# POWER.net
KiCad netlist of a schematic drawn in Altium Designer
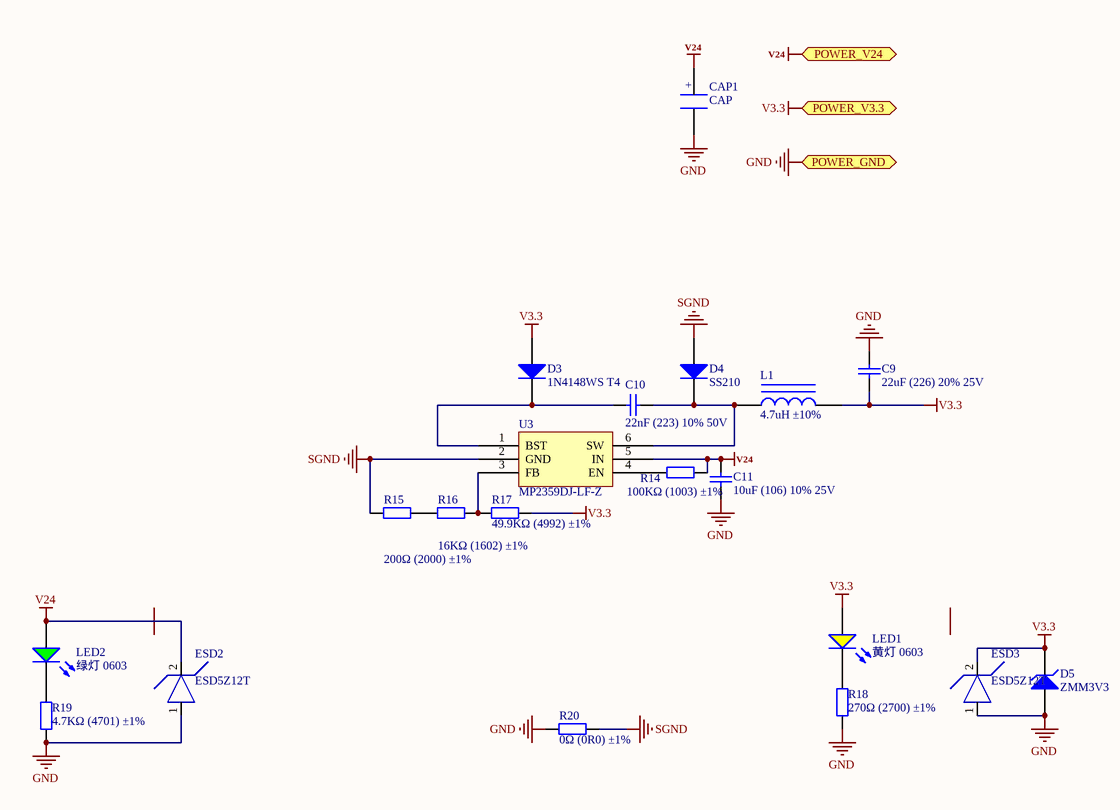
[diagram p0: POWER.SchDoc]

(export (version "E")
  (design (tool "Eeschema 10.0.6"))
  (components
    (comp (ref "C9")
      (value "22uF (226) 20% 25V")
      (footprint "0805_C")
      (description "贴片电容")
      (libsource (lib "Miscellaneous Devices LC") (part "0805 22uF (226) 20% 25V"))
    )
    (comp (ref "C10")
      (value "22nF (223) 10% 50V")
      (footprint "0603_C")
      (description "贴片电容")
      (libsource (lib "Miscellaneous Devices LC") (part "0603 22nF (223) 10% 50V"))
    )
    (comp (ref "C11")
      (value "10uF (106) 10% 25V")
      (footprint "0805_C")
      (description "贴片电容")
      (libsource (lib "Miscellaneous Devices LC") (part "0805 10uF (106) 10% 25V"))
    )
    (comp (ref "CAP1") (value "CAP") (footprint "8X12_CAP") (libsource (lib "mylib") (part "CAP")))
    (comp (ref "D3")
      (value "1N4148WS T4")
      (footprint "SOD-323")
      (description "二极管")
      (libsource (lib "Miscellaneous Devices LC") (part "SOD-323 1N4148WS T4"))
    )
    (comp (ref "D4")
      (value "SS210")
      (footprint "SMA(DO-214AC)_S1")
      (description "二极管")
      (libsource (lib "Miscellaneous Devices LC") (part "SMA(DO-214AC) SS210"))
    )
    (comp (ref "D5")
      (value "ZMM3V3")
      (footprint "LL-34")
      (description "稳压二极管")
      (libsource (lib "Miscellaneous Devices LC") (part "LL-34 ZMM3V3"))
    )
    (comp (ref "ESD2") (value "ESD5Z12T") (footprint "SOD-523") (libsource (lib "mylib") (part "ESD-D")))
    (comp (ref "ESD3") (value "ESD5Z12T") (footprint "SOD-523") (libsource (lib "mylib") (part "ESD-D")))
    (comp (ref "L1")
      (value "4.7uH ±10%")
      (footprint "L_4030")
      (description "贴片电感")
      (libsource (lib "Miscellaneous Devices LC") (part "0603 4.7uH 10%"))
    )
    (comp (ref "LED1")
      (value "黄灯 0603")
      (footprint "0603_LED_S1")
      (description "发光二极管")
      (libsource (lib "Miscellaneous Devices LC") (part "0603 黄灯"))
    )
    (comp (ref "LED2")
      (value "绿灯 0603")
      (footprint "0603_LED_S1")
      (description "发光二极管")
      (libsource (lib "Miscellaneous Devices LC") (part "0603 绿灯"))
    )
    (comp (ref "R14")
      (value "100KΩ (1003) ±1%")
      (footprint "0603_R")
      (description "贴片电阻")
      (libsource (lib "Miscellaneous Devices LC") (part "0603 100KΩ (1003) 1%"))
    )
    (comp (ref "R15")
      (value "200Ω (2000) ±1%")
      (footprint "0603_R")
      (description "贴片电阻")
      (libsource (lib "Miscellaneous Devices LC") (part "0603 200Ω (2000) 1%"))
    )
    (comp (ref "R16")
      (value "16KΩ (1602) ±1%")
      (footprint "0603_R")
      (description "贴片电阻")
      (libsource (lib "Miscellaneous Devices LC") (part "0603 16KΩ (1602) 1%"))
    )
    (comp (ref "R17")
      (value "49.9KΩ (4992) ±1%")
      (footprint "0603_R")
      (description "贴片电阻")
      (libsource (lib "Miscellaneous Devices LC") (part "0603 49.9KΩ (4992) 1%"))
    )
    (comp (ref "R18")
      (value "270Ω (2700) ±1%")
      (footprint "0805_R")
      (description "贴片电阻")
      (libsource (lib "Miscellaneous Devices LC") (part "0805 270Ω (2700) 1%"))
    )
    (comp (ref "R19")
      (value "4.7KΩ (4701) ±1%")
      (footprint "0805_R")
      (description "贴片电阻")
      (libsource (lib "Miscellaneous Devices LC") (part "0805 4.7KΩ (4701) 1%"))
    )
    (comp (ref "R20")
      (value "0Ω (0R0) ±1%")
      (footprint "0603_R")
      (description "贴片电阻")
      (libsource (lib "Miscellaneous Devices LC") (part "0603 0Ω (0R0) 1%"))
    )
    (comp (ref "U3")
      (value "MP2359DJ-LF-Z")
      (footprint "SOT-23-6")
      (description "DC-DC芯片")
      (libsource (lib "Miscellaneous Devices LC") (part "MP2359DJ-LF-Z_[C14259]"))
    )
  )
  (nets
    (net (code "1") (name "GND") (class "Default")
      (node (ref "C11") (pin "1") (pinfunction "1_1") (pintype "passive"))
      (node (ref "C9") (pin "2") (pinfunction "2_2") (pintype "passive"))
      (node (ref "CAP1") (pin "2") (pinfunction "2_2") (pintype "passive"))
      (node (ref "D5") (pin "1") (pinfunction "A_1") (pintype "passive"))
      (node (ref "ESD2") (pin "1") (pinfunction "1_1") (pintype "passive"))
      (node (ref "ESD3") (pin "1") (pinfunction "1_1") (pintype "passive"))
      (node (ref "R18") (pin "1") (pinfunction "1_1") (pintype "passive"))
      (node (ref "R19") (pin "1") (pinfunction "1_1") (pintype "passive"))
      (node (ref "R20") (pin "1") (pinfunction "1_1") (pintype "passive"))
    )
    (net (code "2") (name "Net-(D3-K)") (class "Default")
      (node (ref "C10") (pin "1") (pinfunction "1_1") (pintype "passive"))
      (node (ref "D3") (pin "2") (pinfunction "K_2") (pintype "passive"))
      (node (ref "U3") (pin "1") (pinfunction "BST_1") (pintype "passive"))
    )
    (net (code "3") (name "Net-(D4-K)") (class "Default")
      (node (ref "C10") (pin "2") (pinfunction "2_2") (pintype "passive"))
      (node (ref "D4") (pin "2") (pinfunction "K_2") (pintype "passive"))
      (node (ref "L1") (pin "1") (pinfunction "1_1") (pintype "passive"))
      (node (ref "U3") (pin "6") (pinfunction "SW_6") (pintype "passive"))
    )
    (net (code "4") (name "Net-(LED1-PadK)") (class "Default")
      (node (ref "LED1") (pin "K") (pinfunction "K_K") (pintype "passive"))
      (node (ref "R18") (pin "2") (pinfunction "2_2") (pintype "passive"))
    )
    (net (code "5") (name "Net-(LED2-PadK)") (class "Default")
      (node (ref "LED2") (pin "K") (pinfunction "K_K") (pintype "passive"))
      (node (ref "R19") (pin "2") (pinfunction "2_2") (pintype "passive"))
    )
    (net (code "6") (name "Net-(R15-Pad1)") (class "Default")
      (node (ref "R15") (pin "1") (pinfunction "1_1") (pintype "passive"))
      (node (ref "R16") (pin "2") (pinfunction "2_2") (pintype "passive"))
    )
    (net (code "7") (name "Net-(U3-EN)") (class "Default")
      (node (ref "R14") (pin "1") (pinfunction "1_1") (pintype "passive"))
      (node (ref "U3") (pin "4") (pinfunction "EN_4") (pintype "passive"))
    )
    (net (code "8") (name "Net-(U3-FB)") (class "Default")
      (node (ref "R16") (pin "1") (pinfunction "1_1") (pintype "passive"))
      (node (ref "R17") (pin "1") (pinfunction "1_1") (pintype "passive"))
      (node (ref "U3") (pin "3") (pinfunction "FB_3") (pintype "passive"))
    )
    (net (code "9") (name "SGND") (class "Default")
      (node (ref "D4") (pin "1") (pinfunction "A_1") (pintype "passive"))
      (node (ref "R15") (pin "2") (pinfunction "2_2") (pintype "passive"))
      (node (ref "R20") (pin "2") (pinfunction "2_2") (pintype "passive"))
      (node (ref "U3") (pin "2") (pinfunction "GND_2") (pintype "passive"))
    )
    (net (code "10") (name "V3.3") (class "Default")
      (node (ref "C9") (pin "1") (pinfunction "1_1") (pintype "passive"))
      (node (ref "D3") (pin "1") (pinfunction "A_1") (pintype "passive"))
      (node (ref "D5") (pin "2") (pinfunction "K_2") (pintype "passive"))
      (node (ref "ESD3") (pin "2") (pinfunction "2_2") (pintype "passive"))
      (node (ref "L1") (pin "2") (pinfunction "2_2") (pintype "passive"))
      (node (ref "LED1") (pin "A") (pinfunction "A_A") (pintype "passive"))
      (node (ref "R17") (pin "2") (pinfunction "2_2") (pintype "passive"))
    )
    (net (code "11") (name "V24") (class "Default")
      (node (ref "C11") (pin "2") (pinfunction "2_2") (pintype "passive"))
      (node (ref "CAP1") (pin "1") (pinfunction "1_1") (pintype "passive"))
      (node (ref "ESD2") (pin "2") (pinfunction "2_2") (pintype "passive"))
      (node (ref "LED2") (pin "A") (pinfunction "A_A") (pintype "passive"))
      (node (ref "R14") (pin "2") (pinfunction "2_2") (pintype "passive"))
      (node (ref "U3") (pin "5") (pinfunction "IN_5") (pintype "passive"))
    )
  )
)
